# Power.net
KiCad netlist of a schematic drawn in Altium Designer
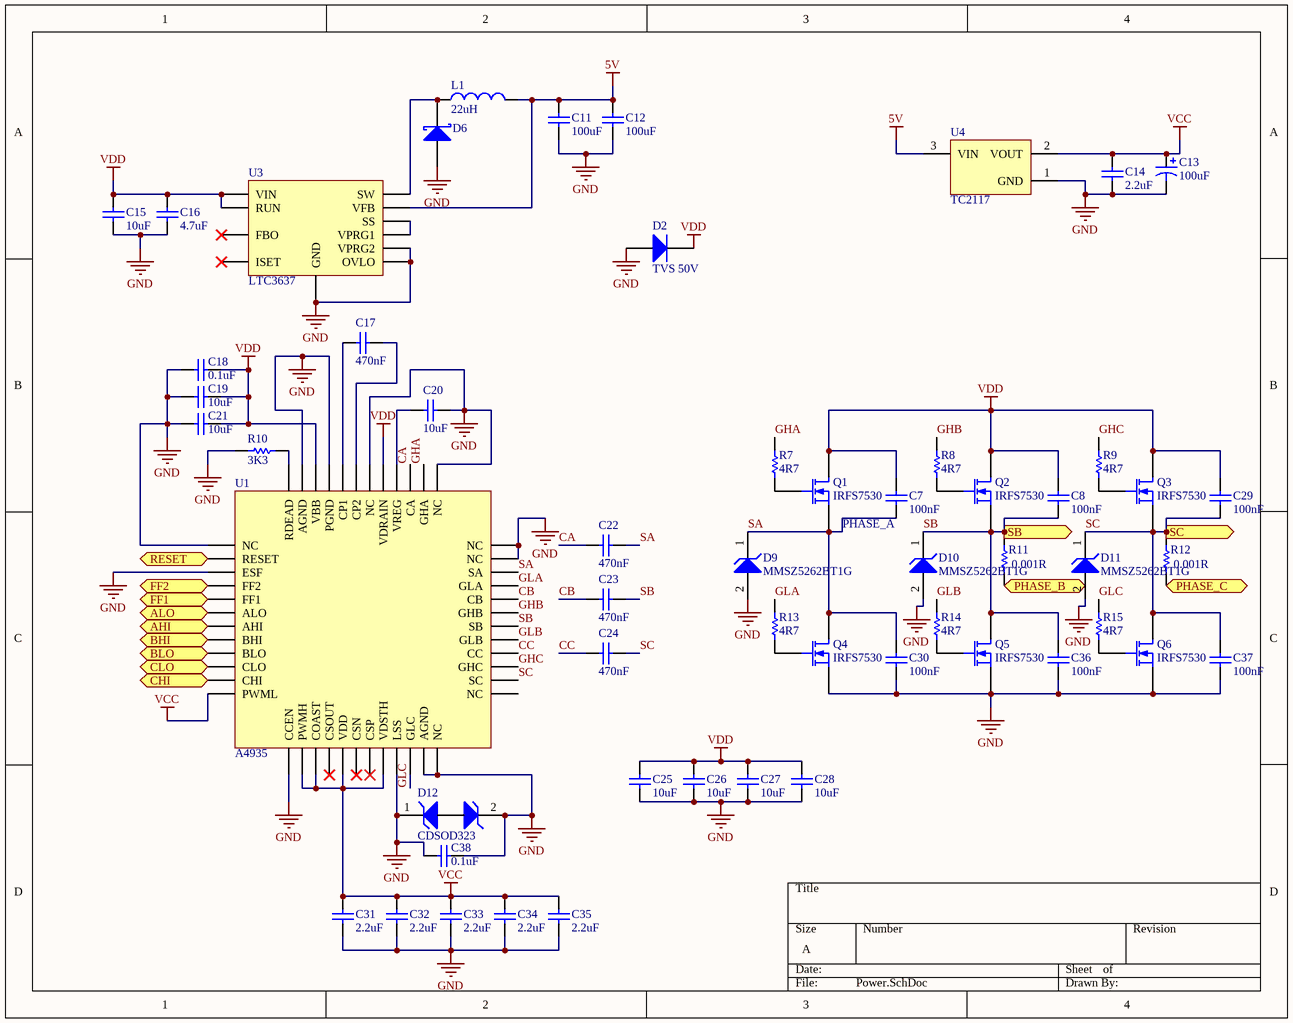
[diagram p0: Power.SchDoc]

(export (version "E")
  (design (tool "Eeschema 10.0.6"))
  (components
    (comp (ref "C7")
      (value "100nF")
      (footprint "CAPC0603(1608)100_L")
      (description "CAP 100nF 50V ±5% 0603 (1608 Metric) Thickness 1mm SMD")
      (fields (field (name "TOLERANCE") "Â±5%"))
      (libsource (lib "Altium Content Vault") (part "CAP"))
    )
    (comp (ref "C8")
      (value "100nF")
      (footprint "CAPC0603(1608)100_L")
      (description "CAP 100nF 50V ±5% 0603 (1608 Metric) Thickness 1mm SMD")
      (fields (field (name "TOLERANCE") "Â±5%"))
      (libsource (lib "Altium Content Vault") (part "CAP"))
    )
    (comp (ref "C11")
      (value "100uF")
      (footprint "CAPC1210(3225)280_N")
      (description "CAP 100uF 10V Â±10% 1210 (3225 Metric) Thickness 2.8mm SMD")
      (fields (field (name "TOLERANCE") "Â±10%"))
      (libsource (lib "Altium Content Vault") (part "CMP-1038-02301-1"))
    )
    (comp (ref "C12")
      (value "100uF")
      (footprint "CAPC1210(3225)280_N")
      (description "CAP 100uF 10V Â±10% 1210 (3225 Metric) Thickness 2.8mm SMD")
      (fields (field (name "TOLERANCE") "Â±10%"))
      (libsource (lib "Altium Content Vault") (part "CMP-1038-02301-1"))
    )
    (comp (ref "C13")
      (value "100uF")
      (footprint "AVX-CAPC7343_V")
      (libsource (lib "Components") (part "AVX-CAP-P-2"))
    )
    (comp (ref "C14")
      (value "2.2uF")
      (footprint "CAPC0603(1608)55_N")
      (description "CAP 2.2uF 16V Â±10% 0603 (1608 Metric) Thickness 0.55mm SMD")
      (fields (field (name "TOLERANCE") "Â±10%"))
      (libsource (lib "Altium Content Vault") (part "CMP-1035-02762-1"))
    )
    (comp (ref "C15")
      (value "10uF")
      (footprint "CAPC1206(3216)190_M")
      (description "CAP 10uF 50V Â±10% 1206 (3216 Metric) Thickness 1.9mm SMD")
      (fields (field (name "TOLERANCE") "Â±10%"))
      (libsource (lib "Altium Content Vault") (part "CAP"))
    )
    (comp (ref "C16")
      (value "4.7uF")
      (footprint "CAPC0805(2012)145_N")
      (description "CAP 4.7uF 50V Â±10% 0805 (2012 Metric) Thickness 1.45mm SMD")
      (fields (field (name "TOLERANCE") "Â±10%"))
      (libsource (lib "Altium Content Vault") (part "CAP"))
    )
    (comp (ref "C17")
      (value "470nF")
      (footprint "CAPC0603(1608)100_N")
      (description "CAP 470nF 25V Â±20% 0603 (1608 Metric) Thickness 1mm SMD")
      (fields (field (name "TOLERANCE") "Â±20%"))
      (libsource (lib "Altium Content Vault") (part "CAP"))
    )
    (comp (ref "C18")
      (value "0.1uF")
      (footprint "CAPC0603(1608)100_L")
      (description "CAP 100nF 50V ±5% 0603 (1608 Metric) Thickness 1mm SMD")
      (fields (field (name "TOLERANCE") "Â±5%"))
      (libsource (lib "Altium Content Vault") (part "CAP"))
    )
    (comp (ref "C19")
      (value "10uF")
      (footprint "CAPC1206(3216)190_M")
      (description "CAP 10uF 50V Â±10% 1206 (3216 Metric) Thickness 1.9mm SMD")
      (fields (field (name "TOLERANCE") "Â±10%"))
      (libsource (lib "Altium Content Vault") (part "CAP"))
    )
    (comp (ref "C20")
      (value "10uF")
      (footprint "CAPC0805(2012)145_N")
      (description "CAP 10uF 25V Â±10% 0805 (2012 Metric) Thickness 1.45mm SMD")
      (fields (field (name "TOLERANCE") "Â±10%"))
      (libsource (lib "Altium Content Vault") (part "CAP"))
    )
    (comp (ref "C21")
      (value "10uF")
      (footprint "CAPC1206(3216)190_M")
      (description "CAP 10uF 50V Â±10% 1206 (3216 Metric) Thickness 1.9mm SMD")
      (fields (field (name "TOLERANCE") "Â±10%"))
      (libsource (lib "Altium Content Vault") (part "CAP"))
    )
    (comp (ref "C22")
      (value "470nF")
      (footprint "CAPC0603(1608)100_L")
      (description "CAP 470nF 25V Â±10% 0603 (1608 Metric) Thickness 1mm SMD")
      (fields (field (name "TOLERANCE") "Â±10%"))
      (libsource (lib "Altium Content Vault") (part "CAP"))
    )
    (comp (ref "C23")
      (value "470nF")
      (footprint "CAPC0603(1608)100_L")
      (description "CAP 470nF 25V Â±10% 0603 (1608 Metric) Thickness 1mm SMD")
      (fields (field (name "TOLERANCE") "Â±10%"))
      (libsource (lib "Altium Content Vault") (part "CAP"))
    )
    (comp (ref "C24")
      (value "470nF")
      (footprint "CAPC0603(1608)100_L")
      (description "CAP 470nF 25V Â±10% 0603 (1608 Metric) Thickness 1mm SMD")
      (fields (field (name "TOLERANCE") "Â±10%"))
      (libsource (lib "Altium Content Vault") (part "CAP"))
    )
    (comp (ref "C25")
      (value "10uF")
      (footprint "CAPC1206(3216)190_M")
      (description "CAP 10uF 50V Â±10% 1206 (3216 Metric) Thickness 1.9mm SMD")
      (fields (field (name "TOLERANCE") "Â±10%"))
      (libsource (lib "Altium Content Vault") (part "CMP-1037-04982-1"))
    )
    (comp (ref "C26")
      (value "10uF")
      (footprint "CAPC1206(3216)190_M")
      (description "CAP 10uF 50V Â±10% 1206 (3216 Metric) Thickness 1.9mm SMD")
      (fields (field (name "TOLERANCE") "Â±10%"))
      (libsource (lib "Altium Content Vault") (part "CAP"))
    )
    (comp (ref "C27")
      (value "10uF")
      (footprint "CAPC1206(3216)190_M")
      (description "CAP 10uF 50V Â±10% 1206 (3216 Metric) Thickness 1.9mm SMD")
      (fields (field (name "TOLERANCE") "Â±10%"))
      (libsource (lib "Altium Content Vault") (part "CAP"))
    )
    (comp (ref "C28")
      (value "10uF")
      (footprint "CAPC1206(3216)190_M")
      (description "CAP 10uF 50V Â±10% 1206 (3216 Metric) Thickness 1.9mm SMD")
      (fields (field (name "TOLERANCE") "Â±10%"))
      (libsource (lib "Altium Content Vault") (part "CMP-1037-04982-1"))
    )
    (comp (ref "C29")
      (value "100nF")
      (footprint "CAPC0603(1608)100_L")
      (description "CAP 100nF 50V ±5% 0603 (1608 Metric) Thickness 1mm SMD")
      (fields (field (name "TOLERANCE") "Â±5%"))
      (libsource (lib "Altium Content Vault") (part "CAP"))
    )
    (comp (ref "C30")
      (value "100nF")
      (footprint "CAPC0603(1608)100_L")
      (description "CAP 100nF 50V ±5% 0603 (1608 Metric) Thickness 1mm SMD")
      (fields (field (name "TOLERANCE") "Â±5%"))
      (libsource (lib "Altium Content Vault") (part "CAP"))
    )
    (comp (ref "C31")
      (value "2.2uF")
      (footprint "CAPC0603(1608)55_N")
      (description "CAP 2.2uF 16V Â±10% 0603 (1608 Metric) Thickness 0.55mm SMD")
      (fields (field (name "TOLERANCE") "Â±10%"))
      (libsource (lib "Altium Content Vault") (part "CMP-1035-02762-1"))
    )
    (comp (ref "C32")
      (value "2.2uF")
      (footprint "CAPC0603(1608)55_N")
      (description "CAP 2.2uF 16V Â±10% 0603 (1608 Metric) Thickness 0.55mm SMD")
      (fields (field (name "TOLERANCE") "Â±10%"))
      (libsource (lib "Altium Content Vault") (part "CMP-1035-02762-1"))
    )
    (comp (ref "C33")
      (value "2.2uF")
      (footprint "CAPC0603(1608)55_N")
      (description "CAP 2.2uF 16V Â±10% 0603 (1608 Metric) Thickness 0.55mm SMD")
      (fields (field (name "TOLERANCE") "Â±10%"))
      (libsource (lib "Altium Content Vault") (part "CMP-1035-02762-1"))
    )
    (comp (ref "C34")
      (value "2.2uF")
      (footprint "CAPC0603(1608)55_N")
      (description "CAP 2.2uF 16V Â±10% 0603 (1608 Metric) Thickness 0.55mm SMD")
      (fields (field (name "TOLERANCE") "Â±10%"))
      (libsource (lib "Altium Content Vault") (part "CMP-1035-02762-1"))
    )
    (comp (ref "C35")
      (value "2.2uF")
      (footprint "CAPC0603(1608)55_N")
      (description "CAP 2.2uF 16V Â±10% 0603 (1608 Metric) Thickness 0.55mm SMD")
      (fields (field (name "TOLERANCE") "Â±10%"))
      (libsource (lib "Altium Content Vault") (part "CMP-1035-02762-1"))
    )
    (comp (ref "C36")
      (value "100nF")
      (footprint "CAPC0603(1608)100_L")
      (description "CAP 100nF 50V ±5% 0603 (1608 Metric) Thickness 1mm SMD")
      (fields (field (name "TOLERANCE") "Â±5%"))
      (libsource (lib "Altium Content Vault") (part "CAP"))
    )
    (comp (ref "C37")
      (value "100nF")
      (footprint "CAPC0603(1608)100_L")
      (description "CAP 100nF 50V ±5% 0603 (1608 Metric) Thickness 1mm SMD")
      (fields (field (name "TOLERANCE") "Â±5%"))
      (libsource (lib "Altium Content Vault") (part "CAP"))
    )
    (comp (ref "C38")
      (value "0.1uF")
      (footprint "CAPC0603(1608)100_M")
      (description "CAP 100nF 6.3V ±5% 0603 (1608 Metric) Thickness 1mm SMD")
      (fields (field (name "TOLERANCE") "Â±5%"))
      (libsource (lib "Altium Content Vault") (part "CAP"))
    )
    (comp (ref "D2")
      (value "TVS 50V")
      (footprint "VISH-DO-214AC-2_N")
      (fields
        (field (name "PARTNUMBER") "SMAJ45A-E3/61")
        (field (name "MANUFACTURER") "Vishay Semiconductor")
      )
      (libsource (lib "Altium Content Vault") (part "CMP-0548-00253-1"))
    )
    (comp (ref "D6")
      (value "~")
      (footprint "SMB")
      (description "Schottky Diode")
      (fields (field (name "PUBLISHER") "Altium Limited"))
      (libsource (lib "Miscellaneous Devices") (part "D Schottky"))
    )
    (comp (ref "D9")
      (value "MMSZ5262BT1G")
      (footprint "ONSC-SOD-123-2-425-04_V")
      (description "Zener Voltage Regulator, 500 mW, 2-Pin SOD-123, Pb-Free, Tape and Reel")
      (fields (field (name "MANUFACTURER") "On Semiconductor"))
      (libsource (lib "Altium Content Vault") (part "CMP-1060-00504-1"))
    )
    (comp (ref "D10")
      (value "MMSZ5262BT1G")
      (footprint "ONSC-SOD-123-2-425-04_V")
      (description "Zener Voltage Regulator, 500 mW, 2-Pin SOD-123, Pb-Free, Tape and Reel")
      (fields (field (name "MANUFACTURER") "On Semiconductor"))
      (libsource (lib "Altium Content Vault") (part "ONSC-K1A2-2"))
    )
    (comp (ref "D11")
      (value "MMSZ5262BT1G")
      (footprint "ONSC-SOD-123-2-425-04_V")
      (description "Zener Voltage Regulator, 500 mW, 2-Pin SOD-123, Pb-Free, Tape and Reel")
      (fields (field (name "MANUFACTURER") "On Semiconductor"))
      (libsource (lib "Altium Content Vault") (part "CMP-1060-00504-1"))
    )
    (comp (ref "D12")
      (value "CDSOD323")
      (footprint "SOD323")
      (description "Zener Voltage Regulator, 500 mW, 2-Pin SOD-123, Pb-Free, Tape and Reel")
      (fields (field (name "PARTNUMBER") "MMSZ5262BT1G") (field (name "MANUFACTURER") "On Semiconductor"))
      (libsource (lib "Components") (part "CDSOD323"))
    )
    (comp (ref "L1")
      (value "22uH")
      (footprint "SDR0805-180ML")
      (description "Inductor")
      (fields (field (name "Comment") "SDR0805-180ML") (field (name "PUBLISHER") "Altium Limited"))
      (libsource (lib "Components") (part "SDR0805-180ML"))
    )
    (comp (ref "Q1")
      (value "IRFS7530")
      (footprint "DPAK127P1525X483-7N")
      (description "N-Channel MOSFET")
      (fields (field (name "PUBLISHER") "Altium Limited"))
      (libsource (lib "Components") (part "IRFS7530"))
    )
    (comp (ref "Q2")
      (value "IRFS7530")
      (footprint "DPAK127P1525X483-7N")
      (description "N-Channel MOSFET")
      (fields (field (name "PUBLISHER") "Altium Limited"))
      (libsource (lib "Components") (part "IRFS7530"))
    )
    (comp (ref "Q3")
      (value "IRFS7530")
      (footprint "DPAK127P1525X483-7N")
      (description "N-Channel MOSFET")
      (fields (field (name "PUBLISHER") "Altium Limited"))
      (libsource (lib "Components") (part "IRFS7530"))
    )
    (comp (ref "Q4")
      (value "IRFS7530")
      (footprint "DPAK127P1525X483-7N")
      (description "N-Channel MOSFET")
      (fields (field (name "PUBLISHER") "Altium Limited"))
      (libsource (lib "Components") (part "IRFS7530"))
    )
    (comp (ref "Q5")
      (value "IRFS7530")
      (footprint "DPAK127P1525X483-7N")
      (description "N-Channel MOSFET")
      (fields (field (name "PUBLISHER") "Altium Limited"))
      (libsource (lib "Components") (part "IRFS7530"))
    )
    (comp (ref "Q6")
      (value "IRFS7530")
      (footprint "DPAK127P1525X483-7N")
      (description "N-Channel MOSFET")
      (fields (field (name "PUBLISHER") "Altium Limited"))
      (libsource (lib "Components") (part "IRFS7530"))
    )
    (comp (ref "R7")
      (value "4R7")
      (footprint "RESC0603(1608)_N")
      (description "4R7 0.1W 5% 0603 (1608 Metric)  SMD")
      (fields (field (name "POWER") "0.1 W") (field (name "TOLERANCE") "5 %"))
      (libsource (lib "Altium Content Vault") (part "CMP-1012-00018-1"))
    )
    (comp (ref "R8")
      (value "4R7")
      (footprint "RESC0603(1608)_N")
      (description "4R7 0.1W 5% 0603 (1608 Metric)  SMD")
      (fields (field (name "POWER") "0.1 W") (field (name "TOLERANCE") "5 %"))
      (libsource (lib "Altium Content Vault") (part "CMP-1012-00018-1"))
    )
    (comp (ref "R9")
      (value "4R7")
      (footprint "RESC0603(1608)_N")
      (description "4R7 0.1W 5% 0603 (1608 Metric)  SMD")
      (fields (field (name "POWER") "0.1 W") (field (name "TOLERANCE") "5 %"))
      (libsource (lib "Altium Content Vault") (part "CMP-1012-00018-1"))
    )
    (comp (ref "R10")
      (value "3K3")
      (footprint "RESC0603(1608)_N")
      (description "3K3 0.1W 5% 0603 (1608 Metric)  SMD")
      (fields (field (name "TOLERANCE") "5 %") (field (name "POWER") "0.1 W"))
      (libsource (lib "Altium Content Vault") (part "CMP-1012-00086-1"))
    )
    (comp (ref "R11")
      (value "0.001R")
      (footprint "Shunt")
      (fields (field (name "PUBLISHER") "Altium Limited"))
      (libsource (lib "Components") (part "Shunt"))
    )
    (comp (ref "R12")
      (value "0.001R")
      (footprint "Shunt")
      (description "Resistor")
      (fields (field (name "PUBLISHER") "Altium Limited"))
      (libsource (lib "Components") (part "Shunt"))
    )
    (comp (ref "R13")
      (value "4R7")
      (footprint "RESC0603(1608)_N")
      (description "4R7 0.1W 5% 0603 (1608 Metric)  SMD")
      (fields (field (name "POWER") "0.1 W") (field (name "TOLERANCE") "5 %"))
      (libsource (lib "Altium Content Vault") (part "CMP-1012-00018-1"))
    )
    (comp (ref "R14")
      (value "4R7")
      (footprint "RESC0603(1608)_N")
      (description "4R7 0.1W 5% 0603 (1608 Metric)  SMD")
      (fields (field (name "POWER") "0.1 W") (field (name "TOLERANCE") "5 %"))
      (libsource (lib "Altium Content Vault") (part "CMP-1012-00018-1"))
    )
    (comp (ref "R15")
      (value "4R7")
      (footprint "RESC0603(1608)_N")
      (description "4R7 0.1W 5% 0603 (1608 Metric)  SMD")
      (fields (field (name "POWER") "0.1 W") (field (name "TOLERANCE") "5 %"))
      (libsource (lib "Altium Content Vault") (part "CMP-1012-00018-1"))
    )
    (comp (ref "U1") (value "A4935") (footprint "LQFP-48") (libsource (lib "Components") (part "A4935")))
    (comp (ref "U3")
      (value "LTC3637")
      (footprint "SON50P300X85_HS-17N")
      (libsource (lib "Components") (part "LTC3637"))
    )
    (comp (ref "U4")
      (value "TC2117")
      (footprint "SOT-223-DB3_M")
      (libsource (lib "Components") (part "PM-LINEREG-TC2117-IL4"))
    )
  )
  (nets
    (net (code "1") (name "/AHI") (class "Default")
      (node (ref "U1") (pin "7") (pinfunction "AHI_7") (pintype "passive"))
    )
    (net (code "2") (name "/ALO") (class "Default")
      (node (ref "U1") (pin "6") (pinfunction "ALO_6") (pintype "passive"))
    )
    (net (code "3") (name "/BHI") (class "Default")
      (node (ref "U1") (pin "8") (pinfunction "BHI_8") (pintype "passive"))
    )
    (net (code "4") (name "/BLO") (class "Default")
      (node (ref "U1") (pin "9") (pinfunction "BLO_9") (pintype "passive"))
    )
    (net (code "5") (name "/CA") (class "Default")
      (node (ref "C22") (pin "1") (pinfunction "1_1") (pintype "passive"))
      (node (ref "U1") (pin "39") (pinfunction "CA_39") (pintype "passive"))
    )
    (net (code "6") (name "/CB") (class "Default")
      (node (ref "C23") (pin "1") (pinfunction "1_1") (pintype "passive"))
      (node (ref "U1") (pin "32") (pinfunction "CB_32") (pintype "passive"))
    )
    (net (code "7") (name "/CC") (class "Default")
      (node (ref "C24") (pin "1") (pinfunction "1_1") (pintype "passive"))
      (node (ref "U1") (pin "28") (pinfunction "CC_28") (pintype "passive"))
    )
    (net (code "8") (name "/CHI") (class "Default")
      (node (ref "U1") (pin "11") (pinfunction "CHI_11") (pintype "passive"))
    )
    (net (code "9") (name "/CLO") (class "Default")
      (node (ref "U1") (pin "10") (pinfunction "CLO_10") (pintype "passive"))
    )
    (net (code "10") (name "/FF1") (class "Default")
      (node (ref "U1") (pin "5") (pinfunction "FF1_5") (pintype "passive"))
    )
    (net (code "11") (name "/FF2") (class "Default")
      (node (ref "U1") (pin "4") (pinfunction "FF2_4") (pintype "passive"))
    )
    (net (code "12") (name "/GHA") (class "Default")
      (node (ref "R7") (pin "2") (pinfunction "2_2") (pintype "passive"))
      (node (ref "U1") (pin "38") (pinfunction "GHA_38") (pintype "passive"))
    )
    (net (code "13") (name "/GHB") (class "Default")
      (node (ref "R8") (pin "2") (pinfunction "2_2") (pintype "passive"))
      (node (ref "U1") (pin "31") (pinfunction "GHB_31") (pintype "passive"))
    )
    (net (code "14") (name "/GHC") (class "Default")
      (node (ref "R9") (pin "2") (pinfunction "2_2") (pintype "passive"))
      (node (ref "U1") (pin "27") (pinfunction "GHC_27") (pintype "passive"))
    )
    (net (code "15") (name "/GLA") (class "Default")
      (node (ref "R13") (pin "2") (pinfunction "2_2") (pintype "passive"))
      (node (ref "U1") (pin "33") (pinfunction "GLA_33") (pintype "passive"))
    )
    (net (code "16") (name "/GLB") (class "Default")
      (node (ref "R14") (pin "2") (pinfunction "2_2") (pintype "passive"))
      (node (ref "U1") (pin "29") (pinfunction "GLB_29") (pintype "passive"))
    )
    (net (code "17") (name "/GLC") (class "Default")
      (node (ref "R15") (pin "2") (pinfunction "2_2") (pintype "passive"))
      (node (ref "U1") (pin "22") (pinfunction "GLC_22") (pintype "passive"))
    )
    (net (code "18") (name "/PHASE_B") (class "Default")
      (node (ref "R11") (pin "1") (pinfunction "1_1") (pintype "passive"))
    )
    (net (code "19") (name "/PHASE_C") (class "Default")
      (node (ref "R12") (pin "1") (pinfunction "1_1") (pintype "passive"))
    )
    (net (code "20") (name "/RESET") (class "Default")
      (node (ref "U1") (pin "2") (pinfunction "RESET_2") (pintype "passive"))
    )
    (net (code "21") (name "/SA") (class "Default")
      (node (ref "C22") (pin "2") (pinfunction "2_2") (pintype "passive"))
      (node (ref "C30") (pin "2") (pinfunction "2_2") (pintype "passive"))
      (node (ref "C7") (pin "1") (pinfunction "1_1") (pintype "passive"))
      (node (ref "D9") (pin "1") (pinfunction "K_1") (pintype "passive"))
      (node (ref "Q1") (pin "3") (pinfunction "S_3") (pintype "passive"))
      (node (ref "Q4") (pin "1") (pinfunction "D_1") (pintype "passive"))
      (node (ref "U1") (pin "34") (pinfunction "SA_34") (pintype "passive"))
    )
    (net (code "22") (name "/SB") (class "Default")
      (node (ref "C23") (pin "2") (pinfunction "2_2") (pintype "passive"))
      (node (ref "C36") (pin "2") (pinfunction "2_2") (pintype "passive"))
      (node (ref "C8") (pin "1") (pinfunction "1_1") (pintype "passive"))
      (node (ref "D10") (pin "1") (pinfunction "K_1") (pintype "passive"))
      (node (ref "Q2") (pin "3") (pinfunction "S_3") (pintype "passive"))
      (node (ref "Q5") (pin "1") (pinfunction "D_1") (pintype "passive"))
      (node (ref "R11") (pin "2") (pinfunction "2_2") (pintype "passive"))
      (node (ref "U1") (pin "30") (pinfunction "SB_30") (pintype "passive"))
    )
    (net (code "23") (name "/SC") (class "Default")
      (node (ref "C24") (pin "2") (pinfunction "2_2") (pintype "passive"))
      (node (ref "C29") (pin "1") (pinfunction "1_1") (pintype "passive"))
      (node (ref "C37") (pin "2") (pinfunction "2_2") (pintype "passive"))
      (node (ref "D11") (pin "1") (pinfunction "K_1") (pintype "passive"))
      (node (ref "Q3") (pin "3") (pinfunction "S_3") (pintype "passive"))
      (node (ref "Q6") (pin "1") (pinfunction "D_1") (pintype "passive"))
      (node (ref "R12") (pin "2") (pinfunction "2_2") (pintype "passive"))
      (node (ref "U1") (pin "26") (pinfunction "SC_26") (pintype "passive"))
    )
    (net (code "24") (name "5V") (class "Default")
      (node (ref "C11") (pin "2") (pinfunction "2_2") (pintype "passive"))
      (node (ref "C12") (pin "2") (pinfunction "2_2") (pintype "passive"))
      (node (ref "L1") (pin "2") (pinfunction "2_2") (pintype "passive"))
      (node (ref "U3") (pin "9") (pinfunction "VFB_9") (pintype "passive"))
      (node (ref "U4") (pin "3") (pinfunction "VIN_3") (pintype "power_in"))
    )
    (net (code "25") (name "GND") (class "Default")
      (node (ref "C11") (pin "1") (pinfunction "1_1") (pintype "passive"))
      (node (ref "C12") (pin "1") (pinfunction "1_1") (pintype "passive"))
      (node (ref "C13") (pin "2") (pinfunction "2_2") (pintype "passive"))
      (node (ref "C14") (pin "2") (pinfunction "2_2") (pintype "passive"))
      (node (ref "C15") (pin "1") (pinfunction "1_1") (pintype "passive"))
      (node (ref "C16") (pin "2") (pinfunction "2_2") (pintype "passive"))
      (node (ref "C18") (pin "1") (pinfunction "1_1") (pintype "passive"))
      (node (ref "C19") (pin "1") (pinfunction "1_1") (pintype "passive"))
      (node (ref "C20") (pin "2") (pinfunction "2_2") (pintype "passive"))
      (node (ref "C21") (pin "1") (pinfunction "1_1") (pintype "passive"))
      (node (ref "C25") (pin "1") (pinfunction "1_1") (pintype "passive"))
      (node (ref "C26") (pin "1") (pinfunction "1_1") (pintype "passive"))
      (node (ref "C27") (pin "1") (pinfunction "1_1") (pintype "passive"))
      (node (ref "C28") (pin "1") (pinfunction "1_1") (pintype "passive"))
      (node (ref "C30") (pin "1") (pinfunction "1_1") (pintype "passive"))
      (node (ref "C31") (pin "1") (pinfunction "1_1") (pintype "passive"))
      (node (ref "C32") (pin "1") (pinfunction "1_1") (pintype "passive"))
      (node (ref "C33") (pin "1") (pinfunction "1_1") (pintype "passive"))
      (node (ref "C34") (pin "1") (pinfunction "1_1") (pintype "passive"))
      (node (ref "C35") (pin "1") (pinfunction "1_1") (pintype "passive"))
      (node (ref "C36") (pin "1") (pinfunction "1_1") (pintype "passive"))
      (node (ref "C37") (pin "1") (pinfunction "1_1") (pintype "passive"))
      (node (ref "C38") (pin "1") (pinfunction "1_1") (pintype "passive"))
      (node (ref "C38") (pin "2") (pinfunction "2_2") (pintype "passive"))
      (node (ref "D10") (pin "2") (pinfunction "A_2") (pintype "passive"))
      (node (ref "D11") (pin "2") (pinfunction "A_2") (pintype "passive"))
      (node (ref "D12") (pin "1") (pinfunction "K_1") (pintype "passive"))
      (node (ref "D12") (pin "2") (pinfunction "K_2") (pintype "passive"))
      (node (ref "D2") (pin "2") (pinfunction "A_2") (pintype "passive"))
      (node (ref "D6") (pin "1") (pinfunction "A_1") (pintype "passive"))
      (node (ref "D9") (pin "2") (pinfunction "A_2") (pintype "passive"))
      (node (ref "Q4") (pin "3") (pinfunction "S_3") (pintype "passive"))
      (node (ref "Q5") (pin "3") (pinfunction "S_3") (pintype "passive"))
      (node (ref "Q6") (pin "3") (pinfunction "S_3") (pintype "passive"))
      (node (ref "R10") (pin "1") (pinfunction "1_1") (pintype "passive"))
      (node (ref "U1") (pin "1") (pinfunction "NC_1") (pintype "passive"))
      (node (ref "U1") (pin "13") (pinfunction "CCEN_13") (pintype "passive"))
      (node (ref "U1") (pin "21") (pinfunction "LSS_21") (pintype "passive"))
      (node (ref "U1") (pin "23") (pinfunction "AGND_23") (pintype "passive"))
      (node (ref "U1") (pin "24") (pinfunction "NC_24") (pintype "passive"))
      (node (ref "U1") (pin "3") (pinfunction "ESF_3") (pintype "passive"))
      (node (ref "U1") (pin "35") (pinfunction "NC_35") (pintype "passive"))
      (node (ref "U1") (pin "36") (pinfunction "NC_36") (pintype "passive"))
      (node (ref "U1") (pin "37") (pinfunction "NC_37") (pintype "passive"))
      (node (ref "U1") (pin "42") (pinfunction "NC_42") (pintype "passive"))
      (node (ref "U1") (pin "45") (pinfunction "PGND_45") (pintype "passive"))
      (node (ref "U1") (pin "47") (pinfunction "AGND_47") (pintype "passive"))
      (node (ref "U3") (pin "12") (pinfunction "OVLO_12") (pintype "passive"))
      (node (ref "U3") (pin "17") (pinfunction "GND_17") (pintype "passive"))
      (node (ref "U3") (pin "6") (pinfunction "VPRG2_6") (pintype "passive"))
      (node (ref "U4") (pin "1") (pinfunction "GND_1") (pintype "power_in"))
    )
    (net (code "26") (name "Net-(D6-K)") (class "Default")
      (node (ref "D6") (pin "2") (pinfunction "K_2") (pintype "passive"))
      (node (ref "L1") (pin "1") (pinfunction "1_1") (pintype "passive"))
      (node (ref "U3") (pin "1") (pinfunction "SW_1") (pintype "passive"))
    )
    (net (code "27") (name "Net-(Q1-G)") (class "Default")
      (node (ref "Q1") (pin "2") (pinfunction "G_2") (pintype "passive"))
      (node (ref "R7") (pin "1") (pinfunction "1_1") (pintype "passive"))
    )
    (net (code "28") (name "Net-(Q2-G)") (class "Default")
      (node (ref "Q2") (pin "2") (pinfunction "G_2") (pintype "passive"))
      (node (ref "R8") (pin "1") (pinfunction "1_1") (pintype "passive"))
    )
    (net (code "29") (name "Net-(Q3-G)") (class "Default")
      (node (ref "Q3") (pin "2") (pinfunction "G_2") (pintype "passive"))
      (node (ref "R9") (pin "1") (pinfunction "1_1") (pintype "passive"))
    )
    (net (code "30") (name "Net-(Q4-G)") (class "Default")
      (node (ref "Q4") (pin "2") (pinfunction "G_2") (pintype "passive"))
      (node (ref "R13") (pin "1") (pinfunction "1_1") (pintype "passive"))
    )
    (net (code "31") (name "Net-(Q5-G)") (class "Default")
      (node (ref "Q5") (pin "2") (pinfunction "G_2") (pintype "passive"))
      (node (ref "R14") (pin "1") (pinfunction "1_1") (pintype "passive"))
    )
    (net (code "32") (name "Net-(Q6-G)") (class "Default")
      (node (ref "Q6") (pin "2") (pinfunction "G_2") (pintype "passive"))
      (node (ref "R15") (pin "1") (pinfunction "1_1") (pintype "passive"))
    )
    (net (code "33") (name "Net-(U1-CP1)") (class "Default")
      (node (ref "C17") (pin "1") (pinfunction "1_1") (pintype "passive"))
      (node (ref "U1") (pin "44") (pinfunction "CP1_44") (pintype "passive"))
    )
    (net (code "34") (name "Net-(U1-CP2)") (class "Default")
      (node (ref "C17") (pin "2") (pinfunction "2_2") (pintype "passive"))
      (node (ref "U1") (pin "43") (pinfunction "CP2_43") (pintype "passive"))
    )
    (net (code "35") (name "Net-(U1-RDEAD)") (class "Default")
      (node (ref "R10") (pin "2") (pinfunction "2_2") (pintype "passive"))
      (node (ref "U1") (pin "48") (pinfunction "RDEAD_48") (pintype "passive"))
    )
    (net (code "36") (name "Net-(U1-VREG)") (class "Default")
      (node (ref "C20") (pin "1") (pinfunction "1_1") (pintype "passive"))
      (node (ref "U1") (pin "40") (pinfunction "VREG_40") (pintype "passive"))
    )
    (net (code "37") (name "Net-(U3-SS)") (class "Default")
      (node (ref "U3") (pin "10") (pinfunction "SS_10") (pintype "passive"))
      (node (ref "U3") (pin "7") (pinfunction "VPRG1_7") (pintype "passive"))
    )
    (net (code "38") (name "VCC") (class "Default")
      (node (ref "C13") (pin "1") (pinfunction "1_1") (pintype "passive"))
      (node (ref "C14") (pin "1") (pinfunction "1_1") (pintype "passive"))
      (node (ref "C31") (pin "2") (pinfunction "2_2") (pintype "passive"))
      (node (ref "C32") (pin "2") (pinfunction "2_2") (pintype "passive"))
      (node (ref "C33") (pin "2") (pinfunction "2_2") (pintype "passive"))
      (node (ref "C34") (pin "2") (pinfunction "2_2") (pintype "passive"))
      (node (ref "C35") (pin "2") (pinfunction "2_2") (pintype "passive"))
      (node (ref "U1") (pin "12") (pinfunction "PWML_12") (pintype "passive"))
      (node (ref "U1") (pin "14") (pinfunction "PWMH_14") (pintype "passive"))
      (node (ref "U1") (pin "15") (pinfunction "COAST_15") (pintype "passive"))
      (node (ref "U1") (pin "17") (pinfunction "VDD_17") (pintype "passive"))
      (node (ref "U1") (pin "20") (pinfunction "VDSTH_20") (pintype "passive"))
      (node (ref "U4") (pin "2") (pinfunction "VOUT_2") (pintype "power_in"))
    )
    (net (code "39") (name "VDD") (class "Default")
      (node (ref "C15") (pin "2") (pinfunction "2_2") (pintype "passive"))
      (node (ref "C16") (pin "1") (pinfunction "1_1") (pintype "passive"))
      (node (ref "C18") (pin "2") (pinfunction "2_2") (pintype "passive"))
      (node (ref "C19") (pin "2") (pinfunction "2_2") (pintype "passive"))
      (node (ref "C21") (pin "2") (pinfunction "2_2") (pintype "passive"))
      (node (ref "C25") (pin "2") (pinfunction "2_2") (pintype "passive"))
      (node (ref "C26") (pin "2") (pinfunction "2_2") (pintype "passive"))
      (node (ref "C27") (pin "2") (pinfunction "2_2") (pintype "passive"))
      (node (ref "C28") (pin "2") (pinfunction "2_2") (pintype "passive"))
      (node (ref "C29") (pin "2") (pinfunction "2_2") (pintype "passive"))
      (node (ref "C7") (pin "2") (pinfunction "2_2") (pintype "passive"))
      (node (ref "C8") (pin "2") (pinfunction "2_2") (pintype "passive"))
      (node (ref "D2") (pin "1") (pinfunction "K_1") (pintype "passive"))
      (node (ref "Q1") (pin "1") (pinfunction "D_1") (pintype "passive"))
      (node (ref "Q2") (pin "1") (pinfunction "D_1") (pintype "passive"))
      (node (ref "Q3") (pin "1") (pinfunction "D_1") (pintype "passive"))
      (node (ref "U1") (pin "41") (pinfunction "VDRAIN_41") (pintype "passive"))
      (node (ref "U1") (pin "46") (pinfunction "VBB_46") (pintype "passive"))
      (node (ref "U3") (pin "14") (pinfunction "RUN_14") (pintype "passive"))
      (node (ref "U3") (pin "3") (pinfunction "VIN_3") (pintype "passive"))
    )
    (net (code "40") (name "unconnected-(U1-CSN-Pad18)") (class "Default")
      (node (ref "U1") (pin "18") (pinfunction "CSN_18") (pintype "passive+no_connect"))
    )
    (net (code "41") (name "unconnected-(U1-CSOUT-Pad16)") (class "Default")
      (node (ref "U1") (pin "16") (pinfunction "CSOUT_16") (pintype "passive+no_connect"))
    )
    (net (code "42") (name "unconnected-(U1-CSP-Pad19)") (class "Default")
      (node (ref "U1") (pin "19") (pinfunction "CSP_19") (pintype "passive+no_connect"))
    )
    (net (code "43") (name "unconnected-(U1-NC-Pad25)") (class "Default")
      (node (ref "U1") (pin "25") (pinfunction "NC_25") (pintype "passive"))
    )
    (net (code "44") (name "unconnected-(U3-FBO-Pad5)") (class "Default")
      (node (ref "U3") (pin "5") (pinfunction "FBO_5") (pintype "passive+no_connect"))
    )
    (net (code "45") (name "unconnected-(U3-ISET-Pad11)") (class "Default")
      (node (ref "U3") (pin "11") (pinfunction "ISET_11") (pintype "passive+no_connect"))
    )
  )
)
